# Board_Connector.net
KiCad netlist of a schematic drawn in Altium Designer
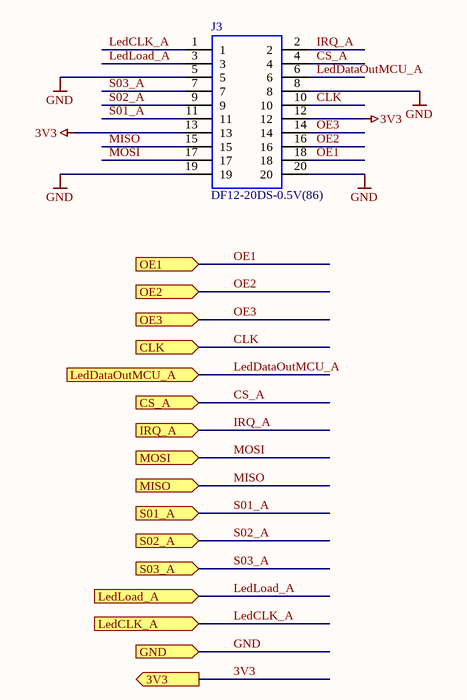
[diagram p0: Board_Connector.SchDoc]

(export (version "E")
  (design (tool "Eeschema 10.0.6"))
  (components
    (comp (ref "J3")
      (value "DF12-20DS-0.5V(86)")
      (footprint "DF12-20DS")
      (fields
        (field (name "MANUFACTURER") "Hirose")
        (field (name "RS PART NUMBER") "1722478")
        (field (name "MOUSER PART NUMBER") "798-DF12-20DS-0.5V86")
      )
      (libsource (lib "RDM_Altium_Library") (part "DF12-20DS-0.5V(86)"))
    )
  )
  (nets
    (net (code "1") (name "/CLK") (class "Default")
      (node (ref "J3") (pin "10") (pinfunction "10_10") (pintype "passive"))
    )
    (net (code "2") (name "/CS_A") (class "Default")
      (node (ref "J3") (pin "4") (pinfunction "4_4") (pintype "passive"))
    )
    (net (code "3") (name "/IRQ_A") (class "Default")
      (node (ref "J3") (pin "2") (pinfunction "2_2") (pintype "passive"))
    )
    (net (code "4") (name "/LedCLK_A") (class "Default")
      (node (ref "J3") (pin "1") (pinfunction "1_1") (pintype "passive"))
    )
    (net (code "5") (name "/LedDataOutMCU_A") (class "Default")
      (node (ref "J3") (pin "6") (pinfunction "6_6") (pintype "passive"))
    )
    (net (code "6") (name "/LedLoad_A") (class "Default")
      (node (ref "J3") (pin "3") (pinfunction "3_3") (pintype "passive"))
    )
    (net (code "7") (name "/MISO") (class "Default")
      (node (ref "J3") (pin "15") (pinfunction "15_15") (pintype "passive"))
    )
    (net (code "8") (name "/MOSI") (class "Default")
      (node (ref "J3") (pin "17") (pinfunction "17_17") (pintype "passive"))
    )
    (net (code "9") (name "/OE1") (class "Default")
      (node (ref "J3") (pin "18") (pinfunction "18_18") (pintype "passive"))
    )
    (net (code "10") (name "/OE2") (class "Default")
      (node (ref "J3") (pin "16") (pinfunction "16_16") (pintype "passive"))
    )
    (net (code "11") (name "/OE3") (class "Default")
      (node (ref "J3") (pin "14") (pinfunction "14_14") (pintype "passive"))
    )
    (net (code "12") (name "/S01_A") (class "Default")
      (node (ref "J3") (pin "11") (pinfunction "11_11") (pintype "passive"))
    )
    (net (code "13") (name "/S02_A") (class "Default")
      (node (ref "J3") (pin "9") (pinfunction "9_9") (pintype "passive"))
    )
    (net (code "14") (name "/S03_A") (class "Default")
      (node (ref "J3") (pin "7") (pinfunction "7_7") (pintype "passive"))
    )
    (net (code "15") (name "3V3") (class "Default")
      (node (ref "J3") (pin "12") (pinfunction "12_12") (pintype "passive"))
      (node (ref "J3") (pin "13") (pinfunction "13_13") (pintype "passive"))
    )
    (net (code "16") (name "GND") (class "Default")
      (node (ref "J3") (pin "19") (pinfunction "19_19") (pintype "passive"))
      (node (ref "J3") (pin "20") (pinfunction "20_20") (pintype "passive"))
      (node (ref "J3") (pin "5") (pinfunction "5_5") (pintype "passive"))
      (node (ref "J3") (pin "8") (pinfunction "8_8") (pintype "passive"))
    )
  )
)
